# ElectrodeBreakout.net
KiCad netlist of a schematic drawn in Altium Designer
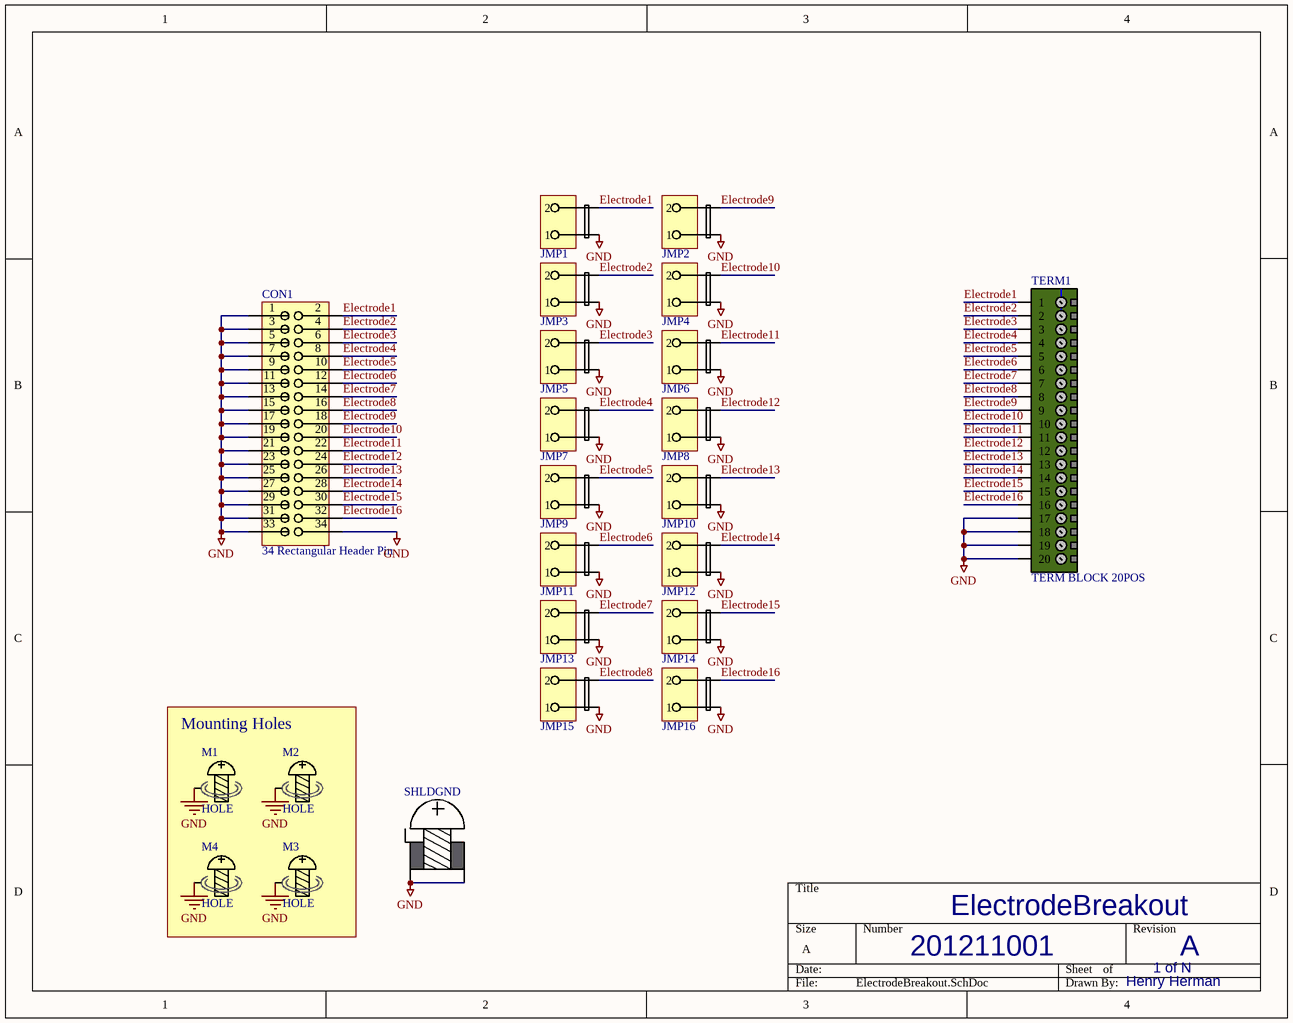
[diagram p0: ElectrodeBreakout.SchDoc]

(export (version "E")
  (design (tool "Eeschema 10.0.6"))
  (components
    (comp (ref "CON1")
      (value "34 Rectangular Header Pin")
      (footprint "34Pin-Rectangular Header-SurfaceMount-100milSpacing")
      (libsource (lib "Henry1_20_2010") (part "34pinHeader"))
    )
    (comp (ref "JMP1")
      (value "JMPR-2PIN-THRU")
      (footprint "M02")
      (libsource (lib "Henry1_20_2010") (part "JMPR-2PIN-THRU"))
    )
    (comp (ref "JMP2")
      (value "JMPR-2PIN-THRU")
      (footprint "M02")
      (libsource (lib "Henry1_20_2010") (part "JMPR-2PIN-THRU"))
    )
    (comp (ref "JMP3")
      (value "JMPR-2PIN-THRU")
      (footprint "M02")
      (libsource (lib "Henry1_20_2010") (part "JMPR-2PIN-THRU"))
    )
    (comp (ref "JMP4")
      (value "JMPR-2PIN-THRU")
      (footprint "M02")
      (libsource (lib "Henry1_20_2010") (part "JMPR-2PIN-THRU"))
    )
    (comp (ref "JMP5")
      (value "JMPR-2PIN-THRU")
      (footprint "M02")
      (libsource (lib "Henry1_20_2010") (part "JMPR-2PIN-THRU"))
    )
    (comp (ref "JMP6")
      (value "JMPR-2PIN-THRU")
      (footprint "M02")
      (libsource (lib "Henry1_20_2010") (part "JMPR-2PIN-THRU"))
    )
    (comp (ref "JMP7")
      (value "JMPR-2PIN-THRU")
      (footprint "M02")
      (libsource (lib "Henry1_20_2010") (part "JMPR-2PIN-THRU"))
    )
    (comp (ref "JMP8")
      (value "JMPR-2PIN-THRU")
      (footprint "M02")
      (libsource (lib "Henry1_20_2010") (part "JMPR-2PIN-THRU"))
    )
    (comp (ref "JMP9")
      (value "JMPR-2PIN-THRU")
      (footprint "M02")
      (libsource (lib "Henry1_20_2010") (part "JMPR-2PIN-THRU"))
    )
    (comp (ref "JMP10")
      (value "JMPR-2PIN-THRU")
      (footprint "M02")
      (libsource (lib "Henry1_20_2010") (part "JMPR-2PIN-THRU"))
    )
    (comp (ref "JMP11")
      (value "JMPR-2PIN-THRU")
      (footprint "M02")
      (libsource (lib "Henry1_20_2010") (part "JMPR-2PIN-THRU"))
    )
    (comp (ref "JMP12")
      (value "JMPR-2PIN-THRU")
      (footprint "M02")
      (libsource (lib "Henry1_20_2010") (part "JMPR-2PIN-THRU"))
    )
    (comp (ref "JMP13")
      (value "JMPR-2PIN-THRU")
      (footprint "M02")
      (libsource (lib "Henry1_20_2010") (part "JMPR-2PIN-THRU"))
    )
    (comp (ref "JMP14")
      (value "JMPR-2PIN-THRU")
      (footprint "M02")
      (libsource (lib "Henry1_20_2010") (part "JMPR-2PIN-THRU"))
    )
    (comp (ref "JMP15")
      (value "JMPR-2PIN-THRU")
      (footprint "M02")
      (libsource (lib "Henry1_20_2010") (part "JMPR-2PIN-THRU"))
    )
    (comp (ref "JMP16")
      (value "JMPR-2PIN-THRU")
      (footprint "M02")
      (libsource (lib "Henry1_20_2010") (part "JMPR-2PIN-THRU"))
    )
    (comp (ref "M1")
      (value "HOLE")
      (footprint "MOUNTING_HOLE-125mil - Thin")
      (libsource (lib "Henry1_20_2010") (part "MountingHole"))
    )
    (comp (ref "M2")
      (value "HOLE")
      (footprint "MOUNTING_HOLE-125mil - Thin")
      (libsource (lib "Henry1_20_2010") (part "MountingHole"))
    )
    (comp (ref "M3")
      (value "HOLE")
      (footprint "MOUNTING_HOLE-125mil - Thin")
      (libsource (lib "Henry1_20_2010") (part "MountingHole"))
    )
    (comp (ref "M4")
      (value "HOLE")
      (footprint "MOUNTING_HOLE-125mil - Thin")
      (libsource (lib "Henry1_20_2010") (part "MountingHole"))
    )
    (comp (ref "SHLDGND")
      (value "SCREW TERM (10-32)")
      (footprint "LOW-PROFILE-SCREWTERMINAL")
      (libsource (lib "Henry1_20_2010") (part "ScrewTerminal-PCB-ThruHole"))
    )
    (comp (ref "TERM1")
      (value "TERM BLOCK 20POS")
      (footprint "EuroStyleConnector-20Pin-3.5mm")
      (libsource (lib "Henry1_20_2010") (part "EuroStyleTerminalBlock_20Pin"))
    )
  )
  (nets
    (net (code "1") (name "/Electrode1") (class "Default")
      (node (ref "CON1") (pin "2") (pinfunction "2_2") (pintype "passive"))
      (node (ref "JMP1") (pin "2") (pinfunction "2_2") (pintype "passive"))
      (node (ref "TERM1") (pin "1") (pinfunction "1_1") (pintype "passive"))
    )
    (net (code "2") (name "/Electrode2") (class "Default")
      (node (ref "CON1") (pin "4") (pinfunction "4_4") (pintype "passive"))
      (node (ref "JMP3") (pin "2") (pinfunction "2_2") (pintype "passive"))
      (node (ref "TERM1") (pin "2") (pinfunction "2_2") (pintype "passive"))
    )
    (net (code "3") (name "/Electrode3") (class "Default")
      (node (ref "CON1") (pin "6") (pinfunction "6_6") (pintype "passive"))
      (node (ref "JMP5") (pin "2") (pinfunction "2_2") (pintype "passive"))
      (node (ref "TERM1") (pin "3") (pinfunction "3_3") (pintype "passive"))
    )
    (net (code "4") (name "/Electrode4") (class "Default")
      (node (ref "CON1") (pin "8") (pinfunction "8_8") (pintype "passive"))
      (node (ref "JMP7") (pin "2") (pinfunction "2_2") (pintype "passive"))
      (node (ref "TERM1") (pin "4") (pinfunction "4_4") (pintype "passive"))
    )
    (net (code "5") (name "/Electrode5") (class "Default")
      (node (ref "CON1") (pin "10") (pinfunction "10_10") (pintype "passive"))
      (node (ref "JMP9") (pin "2") (pinfunction "2_2") (pintype "passive"))
      (node (ref "TERM1") (pin "5") (pinfunction "5_5") (pintype "passive"))
    )
    (net (code "6") (name "/Electrode6") (class "Default")
      (node (ref "CON1") (pin "12") (pinfunction "12_12") (pintype "passive"))
      (node (ref "JMP11") (pin "2") (pinfunction "2_2") (pintype "passive"))
      (node (ref "TERM1") (pin "6") (pinfunction "6_6") (pintype "passive"))
    )
    (net (code "7") (name "/Electrode7") (class "Default")
      (node (ref "CON1") (pin "14") (pinfunction "14_14") (pintype "passive"))
      (node (ref "JMP13") (pin "2") (pinfunction "2_2") (pintype "passive"))
      (node (ref "TERM1") (pin "7") (pinfunction "7_7") (pintype "passive"))
    )
    (net (code "8") (name "/Electrode8") (class "Default")
      (node (ref "CON1") (pin "16") (pinfunction "16_16") (pintype "passive"))
      (node (ref "JMP15") (pin "2") (pinfunction "2_2") (pintype "passive"))
      (node (ref "TERM1") (pin "8") (pinfunction "8_8") (pintype "passive"))
    )
    (net (code "9") (name "/Electrode9") (class "Default")
      (node (ref "CON1") (pin "18") (pinfunction "18_18") (pintype "passive"))
      (node (ref "JMP2") (pin "2") (pinfunction "2_2") (pintype "passive"))
      (node (ref "TERM1") (pin "9") (pinfunction "9_9") (pintype "passive"))
    )
    (net (code "10") (name "/Electrode10") (class "Default")
      (node (ref "CON1") (pin "20") (pinfunction "20_20") (pintype "passive"))
      (node (ref "JMP4") (pin "2") (pinfunction "2_2") (pintype "passive"))
      (node (ref "TERM1") (pin "10") (pinfunction "10_10") (pintype "passive"))
    )
    (net (code "11") (name "/Electrode11") (class "Default")
      (node (ref "CON1") (pin "22") (pinfunction "22_22") (pintype "passive"))
      (node (ref "JMP6") (pin "2") (pinfunction "2_2") (pintype "passive"))
      (node (ref "TERM1") (pin "11") (pinfunction "11_11") (pintype "passive"))
    )
    (net (code "12") (name "/Electrode12") (class "Default")
      (node (ref "CON1") (pin "24") (pinfunction "24_24") (pintype "passive"))
      (node (ref "JMP8") (pin "2") (pinfunction "2_2") (pintype "passive"))
      (node (ref "TERM1") (pin "12") (pinfunction "12_12") (pintype "passive"))
    )
    (net (code "13") (name "/Electrode13") (class "Default")
      (node (ref "CON1") (pin "26") (pinfunction "26_26") (pintype "passive"))
      (node (ref "JMP10") (pin "2") (pinfunction "2_2") (pintype "passive"))
      (node (ref "TERM1") (pin "13") (pinfunction "13_13") (pintype "passive"))
    )
    (net (code "14") (name "/Electrode14") (class "Default")
      (node (ref "CON1") (pin "28") (pinfunction "28_28") (pintype "passive"))
      (node (ref "JMP12") (pin "2") (pinfunction "2_2") (pintype "passive"))
      (node (ref "TERM1") (pin "14") (pinfunction "14_14") (pintype "passive"))
    )
    (net (code "15") (name "/Electrode15") (class "Default")
      (node (ref "CON1") (pin "30") (pinfunction "30_30") (pintype "passive"))
      (node (ref "JMP14") (pin "2") (pinfunction "2_2") (pintype "passive"))
      (node (ref "TERM1") (pin "15") (pinfunction "15_15") (pintype "passive"))
    )
    (net (code "16") (name "/Electrode16") (class "Default")
      (node (ref "CON1") (pin "32") (pinfunction "32_32") (pintype "passive"))
      (node (ref "JMP16") (pin "2") (pinfunction "2_2") (pintype "passive"))
      (node (ref "TERM1") (pin "16") (pinfunction "16_16") (pintype "passive"))
    )
    (net (code "17") (name "GND") (class "Default")
      (node (ref "CON1") (pin "1") (pinfunction "1_1") (pintype "passive"))
      (node (ref "CON1") (pin "11") (pinfunction "11_11") (pintype "passive"))
      (node (ref "CON1") (pin "13") (pinfunction "13_13") (pintype "passive"))
      (node (ref "CON1") (pin "15") (pinfunction "15_15") (pintype "passive"))
      (node (ref "CON1") (pin "17") (pinfunction "17_17") (pintype "passive"))
      (node (ref "CON1") (pin "19") (pinfunction "19_19") (pintype "passive"))
      (node (ref "CON1") (pin "21") (pinfunction "21_21") (pintype "passive"))
      (node (ref "CON1") (pin "23") (pinfunction "23_23") (pintype "passive"))
      (node (ref "CON1") (pin "25") (pinfunction "25_25") (pintype "passive"))
      (node (ref "CON1") (pin "27") (pinfunction "27_27") (pintype "passive"))
      (node (ref "CON1") (pin "29") (pinfunction "29_29") (pintype "passive"))
      (node (ref "CON1") (pin "3") (pinfunction "3_3") (pintype "passive"))
      (node (ref "CON1") (pin "31") (pinfunction "31_31") (pintype "passive"))
      (node (ref "CON1") (pin "33") (pinfunction "33_33") (pintype "passive"))
      (node (ref "CON1") (pin "34") (pinfunction "34_34") (pintype "passive"))
      (node (ref "CON1") (pin "5") (pinfunction "5_5") (pintype "passive"))
      (node (ref "CON1") (pin "7") (pinfunction "7_7") (pintype "passive"))
      (node (ref "CON1") (pin "9") (pinfunction "9_9") (pintype "passive"))
      (node (ref "JMP1") (pin "1") (pinfunction "1_1") (pintype "passive"))
      (node (ref "JMP10") (pin "1") (pinfunction "1_1") (pintype "passive"))
      (node (ref "JMP11") (pin "1") (pinfunction "1_1") (pintype "passive"))
      (node (ref "JMP12") (pin "1") (pinfunction "1_1") (pintype "passive"))
      (node (ref "JMP13") (pin "1") (pinfunction "1_1") (pintype "passive"))
      (node (ref "JMP14") (pin "1") (pinfunction "1_1") (pintype "passive"))
      (node (ref "JMP15") (pin "1") (pinfunction "1_1") (pintype "passive"))
      (node (ref "JMP16") (pin "1") (pinfunction "1_1") (pintype "passive"))
      (node (ref "JMP2") (pin "1") (pinfunction "1_1") (pintype "passive"))
      (node (ref "JMP3") (pin "1") (pinfunction "1_1") (pintype "passive"))
      (node (ref "JMP4") (pin "1") (pinfunction "1_1") (pintype "passive"))
      (node (ref "JMP5") (pin "1") (pinfunction "1_1") (pintype "passive"))
      (node (ref "JMP6") (pin "1") (pinfunction "1_1") (pintype "passive"))
      (node (ref "JMP7") (pin "1") (pinfunction "1_1") (pintype "passive"))
      (node (ref "JMP8") (pin "1") (pinfunction "1_1") (pintype "passive"))
      (node (ref "JMP9") (pin "1") (pinfunction "1_1") (pintype "passive"))
      (node (ref "M1") (pin "0") (pinfunction "PAD_0") (pintype "power_in"))
      (node (ref "M2") (pin "0") (pinfunction "PAD_0") (pintype "power_in"))
      (node (ref "M3") (pin "0") (pinfunction "PAD_0") (pintype "power_in"))
      (node (ref "M4") (pin "0") (pinfunction "PAD_0") (pintype "power_in"))
      (node (ref "SHLDGND") (pin "1") (pintype "passive"))
      (node (ref "TERM1") (pin "17") (pinfunction "17_17") (pintype "passive"))
      (node (ref "TERM1") (pin "18") (pinfunction "18_18") (pintype "passive"))
      (node (ref "TERM1") (pin "19") (pinfunction "19_19") (pintype "passive"))
      (node (ref "TERM1") (pin "20") (pinfunction "20_20") (pintype "passive"))
    )
  )
)
